# DSI_LCD.net
KiCad netlist of a schematic drawn in Altium Designer
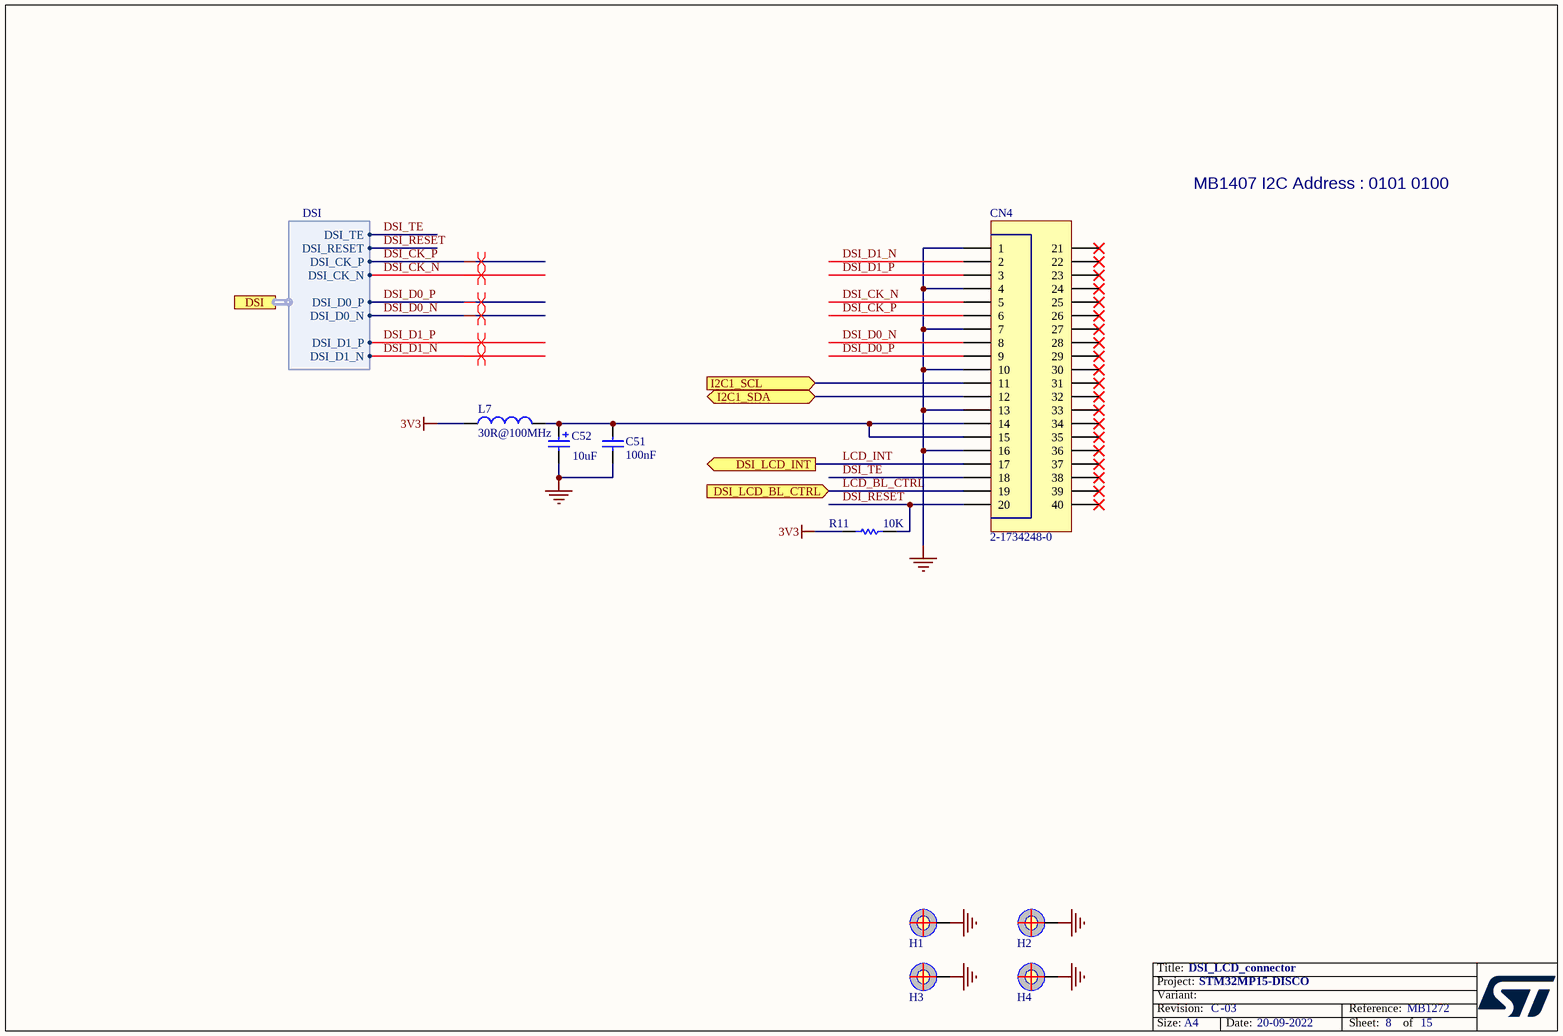
[diagram p0: DSI_LCD.SchDoc]

(export (version "E")
  (design (tool "Eeschema 10.0.6"))
  (components
    (comp (ref "C51")
      (value "100nF")
      (footprint "C0402")
      (description "Capacitor,100nF,16V,X7R,10%,0402")
      (fields
        (field (name "INTERNAL_PART_NUMBER") "MCD-00006")
        (field (name "MANUFACTURER_PART_NUMBER") "CC0402KRX7R7BB104")
        (field (name "PROVIDED_BY") "SUBCO")
      )
      (libsource (lib "MCD_PARTS_database") (part "Capacitor"))
    )
    (comp (ref "C52")
      (value "10uF")
      (footprint "CPOL_TAJ-A_1206_H180")
      (description "Polarized Capacitor,10uF,16V,10%,typeA")
      (fields
        (field (name "INTERNAL_PART_NUMBER") "MCD-00199")
        (field (name "MANUFACTURER_PART_NUMBER") "TAJA106K016R")
        (field (name "PROVIDED_BY") "SUBCO")
      )
      (libsource (lib "MCD_PARTS_database") (part "Cap_POL_TANA"))
    )
    (comp (ref "CN4")
      (value "2-1734248-0")
      (footprint "CON_TE-CONNECTIVITY_2-1734248-0")
      (description "Socket ,TEConn,FCC/FPC, 20pins, 1.0mm,SMT, ZIF Receptacle")
      (fields
        (field (name "INTERNAL_PART_NUMBER") "MCD-01013")
        (field (name "MANUFACTURER") "TE CONNECTIVITY")
        (field (name "PROVIDED_BY") "SUBCO")
      )
      (libsource (lib "MCD_PARTS_database") (part "2-1734248-0"))
    )
    (comp (ref "H1")
      (value "~")
      (footprint "PTH_M1261-3005-N_3P5X6_M3_H14")
      (description "POSITION HOLE C6D3R5")
      (fields (field (name "INTERNAL_PART_NUMBER") "MCD-00035") (field (name "MANUFACTURER") "n/a"))
      (libsource (lib "MCD_PARTS_database") (part "POSITION HOLE C6D3R5"))
    )
    (comp (ref "H2")
      (value "~")
      (footprint "PTH_M1261-3005-N_3P5X6_M3_H14")
      (description "POSITION HOLE C6D3R5")
      (fields (field (name "INTERNAL_PART_NUMBER") "MCD-00035") (field (name "MANUFACTURER") "n/a"))
      (libsource (lib "MCD_PARTS_database") (part "POSITION HOLE C6D3R5"))
    )
    (comp (ref "H3")
      (value "~")
      (footprint "PTH_M1261-3005-N_3P5X6_M3_H14")
      (description "POSITION HOLE C6D3R5")
      (fields (field (name "INTERNAL_PART_NUMBER") "MCD-00035") (field (name "MANUFACTURER") "n/a"))
      (libsource (lib "MCD_PARTS_database") (part "POSITION HOLE C6D3R5"))
    )
    (comp (ref "H4")
      (value "~")
      (footprint "PTH_M1261-3005-N_3P5X6_M3_H14")
      (description "POSITION HOLE C6D3R5")
      (fields (field (name "INTERNAL_PART_NUMBER") "MCD-00035") (field (name "MANUFACTURER") "n/a"))
      (libsource (lib "MCD_PARTS_database") (part "POSITION HOLE C6D3R5"))
    )
    (comp (ref "L7")
      (value "30R@100MHz")
      (footprint "L0603")
      (description "SMD Chip ferrite bead, 30R@100MHz +/-30%, 5A, 10mohm DC, S (Standard) material, 0603, T=0.8mm")
      (fields
        (field (name "INTERNAL_PART_NUMBER") "MCD-00046")
        (field (name "MANUFACTURER_PART_NUMBER") "MPZ1608S300A")
        (field (name "PROVIDED_BY") "SUBCO")
      )
      (libsource (lib "MCD_PARTS_database") (part "BEAD"))
    )
    (comp (ref "R11")
      (value "10K")
      (footprint "R0402")
      (description "Resistor,10K,0402,1%,1/16W")
      (fields
        (field (name "INTERNAL_PART_NUMBER") "MCD-00053")
        (field (name "MANUFACTURER_PART_NUMBER") "RC0402FR-0710KL")
        (field (name "PROVIDED_BY") "SUBCO")
      )
      (libsource (lib "MCD_PARTS_database") (part "Resistor"))
    )
  )
  (nets
    (net (code "2") (name "/DSI_CK_N") (class "Default")
      (node (ref "CN4") (pin "5") (pinfunction "5_5") (pintype "passive"))
    )
    (net (code "3") (name "/DSI_CK_P") (class "Default")
      (node (ref "CN4") (pin "6") (pinfunction "6_6") (pintype "passive"))
    )
    (net (code "4") (name "/DSI_D0_N") (class "Default")
      (node (ref "CN4") (pin "8") (pinfunction "8_8") (pintype "passive"))
    )
    (net (code "5") (name "/DSI_D0_P") (class "Default")
      (node (ref "CN4") (pin "9") (pinfunction "9_9") (pintype "passive"))
    )
    (net (code "6") (name "/DSI_D1_N") (class "Default")
      (node (ref "CN4") (pin "2") (pinfunction "2_2") (pintype "passive"))
    )
    (net (code "7") (name "/DSI_D1_P") (class "Default")
      (node (ref "CN4") (pin "3") (pinfunction "3_3") (pintype "passive"))
    )
    (net (code "8") (name "/DSI_RESET") (class "Default")
      (node (ref "CN4") (pin "20") (pinfunction "20_20") (pintype "passive"))
      (node (ref "R11") (pin "2") (pinfunction "2_2") (pintype "passive"))
    )
    (net (code "9") (name "/DSI_TE") (class "Default")
      (node (ref "CN4") (pin "18") (pinfunction "18_18") (pintype "passive"))
    )
    (net (code "10") (name "/I2C1_SCL") (class "Default")
      (node (ref "CN4") (pin "11") (pinfunction "11_11") (pintype "passive"))
    )
    (net (code "11") (name "/I2C1_SDA") (class "Default")
      (node (ref "CN4") (pin "12") (pinfunction "12_12") (pintype "passive"))
    )
    (net (code "12") (name "/LCD_BL_CTRL") (class "Default")
      (node (ref "CN4") (pin "19") (pinfunction "19_19") (pintype "passive"))
    )
    (net (code "13") (name "/LCD_INT") (class "Default")
      (node (ref "CN4") (pin "17") (pinfunction "17_17") (pintype "passive"))
    )
    (net (code "15") (name "3V3") (class "Default")
      (node (ref "L7") (pin "1") (pinfunction "1_1") (pintype "passive"))
      (node (ref "R11") (pin "1") (pinfunction "1_1") (pintype "passive"))
    )
    (net (code "16") (name "GND") (class "Default")
      (node (ref "C51") (pin "1") (pinfunction "1_1") (pintype "passive"))
      (node (ref "C52") (pin "2") (pinfunction "2_2") (pintype "passive"))
      (node (ref "CN4") (pin "1") (pinfunction "1_1") (pintype "passive"))
      (node (ref "CN4") (pin "10") (pinfunction "10_10") (pintype "passive"))
      (node (ref "CN4") (pin "13") (pinfunction "13_13") (pintype "passive"))
      (node (ref "CN4") (pin "16") (pinfunction "16_16") (pintype "passive"))
      (node (ref "CN4") (pin "4") (pinfunction "4_4") (pintype "passive"))
      (node (ref "CN4") (pin "7") (pinfunction "7_7") (pintype "passive"))
      (node (ref "H1") (pin "1") (pinfunction "1_1") (pintype "passive"))
      (node (ref "H2") (pin "1") (pinfunction "1_1") (pintype "passive"))
      (node (ref "H3") (pin "1") (pinfunction "1_1") (pintype "passive"))
      (node (ref "H4") (pin "1") (pinfunction "1_1") (pintype "passive"))
    )
    (net (code "17") (name "Net-(C51-Pad2)") (class "Default")
      (node (ref "C51") (pin "2") (pinfunction "2_2") (pintype "passive"))
      (node (ref "C52") (pin "1") (pinfunction "1_1") (pintype "passive"))
      (node (ref "CN4") (pin "14") (pinfunction "14_14") (pintype "passive"))
      (node (ref "CN4") (pin "15") (pinfunction "15_15") (pintype "passive"))
      (node (ref "L7") (pin "2") (pinfunction "2_2") (pintype "passive"))
    )
    (net (code "18") (name "unconnected-(CN4-Pad21)") (class "Default")
      (node (ref "CN4") (pin "21") (pinfunction "21_21") (pintype "passive+no_connect"))
    )
    (net (code "19") (name "unconnected-(CN4-Pad22)") (class "Default")
      (node (ref "CN4") (pin "22") (pinfunction "22_22") (pintype "passive+no_connect"))
    )
    (net (code "20") (name "unconnected-(CN4-Pad23)") (class "Default")
      (node (ref "CN4") (pin "23") (pinfunction "23_23") (pintype "passive+no_connect"))
    )
    (net (code "21") (name "unconnected-(CN4-Pad24)") (class "Default")
      (node (ref "CN4") (pin "24") (pinfunction "24_24") (pintype "passive+no_connect"))
    )
    (net (code "22") (name "unconnected-(CN4-Pad25)") (class "Default")
      (node (ref "CN4") (pin "25") (pinfunction "25_25") (pintype "passive+no_connect"))
    )
    (net (code "23") (name "unconnected-(CN4-Pad26)") (class "Default")
      (node (ref "CN4") (pin "26") (pinfunction "26_26") (pintype "passive+no_connect"))
    )
    (net (code "24") (name "unconnected-(CN4-Pad27)") (class "Default")
      (node (ref "CN4") (pin "27") (pinfunction "27_27") (pintype "passive+no_connect"))
    )
    (net (code "25") (name "unconnected-(CN4-Pad28)") (class "Default")
      (node (ref "CN4") (pin "28") (pinfunction "28_28") (pintype "passive+no_connect"))
    )
    (net (code "26") (name "unconnected-(CN4-Pad29)") (class "Default")
      (node (ref "CN4") (pin "29") (pinfunction "29_29") (pintype "passive+no_connect"))
    )
    (net (code "27") (name "unconnected-(CN4-Pad30)") (class "Default")
      (node (ref "CN4") (pin "30") (pinfunction "30_30") (pintype "passive+no_connect"))
    )
    (net (code "28") (name "unconnected-(CN4-Pad31)") (class "Default")
      (node (ref "CN4") (pin "31") (pinfunction "31_31") (pintype "passive+no_connect"))
    )
    (net (code "29") (name "unconnected-(CN4-Pad32)") (class "Default")
      (node (ref "CN4") (pin "32") (pinfunction "32_32") (pintype "passive+no_connect"))
    )
    (net (code "30") (name "unconnected-(CN4-Pad33)") (class "Default")
      (node (ref "CN4") (pin "33") (pinfunction "33_33") (pintype "passive+no_connect"))
    )
    (net (code "31") (name "unconnected-(CN4-Pad34)") (class "Default")
      (node (ref "CN4") (pin "34") (pinfunction "34_34") (pintype "passive+no_connect"))
    )
    (net (code "32") (name "unconnected-(CN4-Pad35)") (class "Default")
      (node (ref "CN4") (pin "35") (pinfunction "35_35") (pintype "passive+no_connect"))
    )
    (net (code "33") (name "unconnected-(CN4-Pad36)") (class "Default")
      (node (ref "CN4") (pin "36") (pinfunction "36_36") (pintype "passive+no_connect"))
    )
    (net (code "34") (name "unconnected-(CN4-Pad37)") (class "Default")
      (node (ref "CN4") (pin "37") (pinfunction "37_37") (pintype "passive+no_connect"))
    )
    (net (code "35") (name "unconnected-(CN4-Pad38)") (class "Default")
      (node (ref "CN4") (pin "38") (pinfunction "38_38") (pintype "passive+no_connect"))
    )
    (net (code "36") (name "unconnected-(CN4-Pad39)") (class "Default")
      (node (ref "CN4") (pin "39") (pinfunction "39_39") (pintype "passive+no_connect"))
    )
    (net (code "37") (name "unconnected-(CN4-Pad40)") (class "Default")
      (node (ref "CN4") (pin "40") (pinfunction "40_40") (pintype "passive+no_connect"))
    )
  )
)
